# BMS_V5.net
KiCad netlist of a schematic drawn in Altium Designer
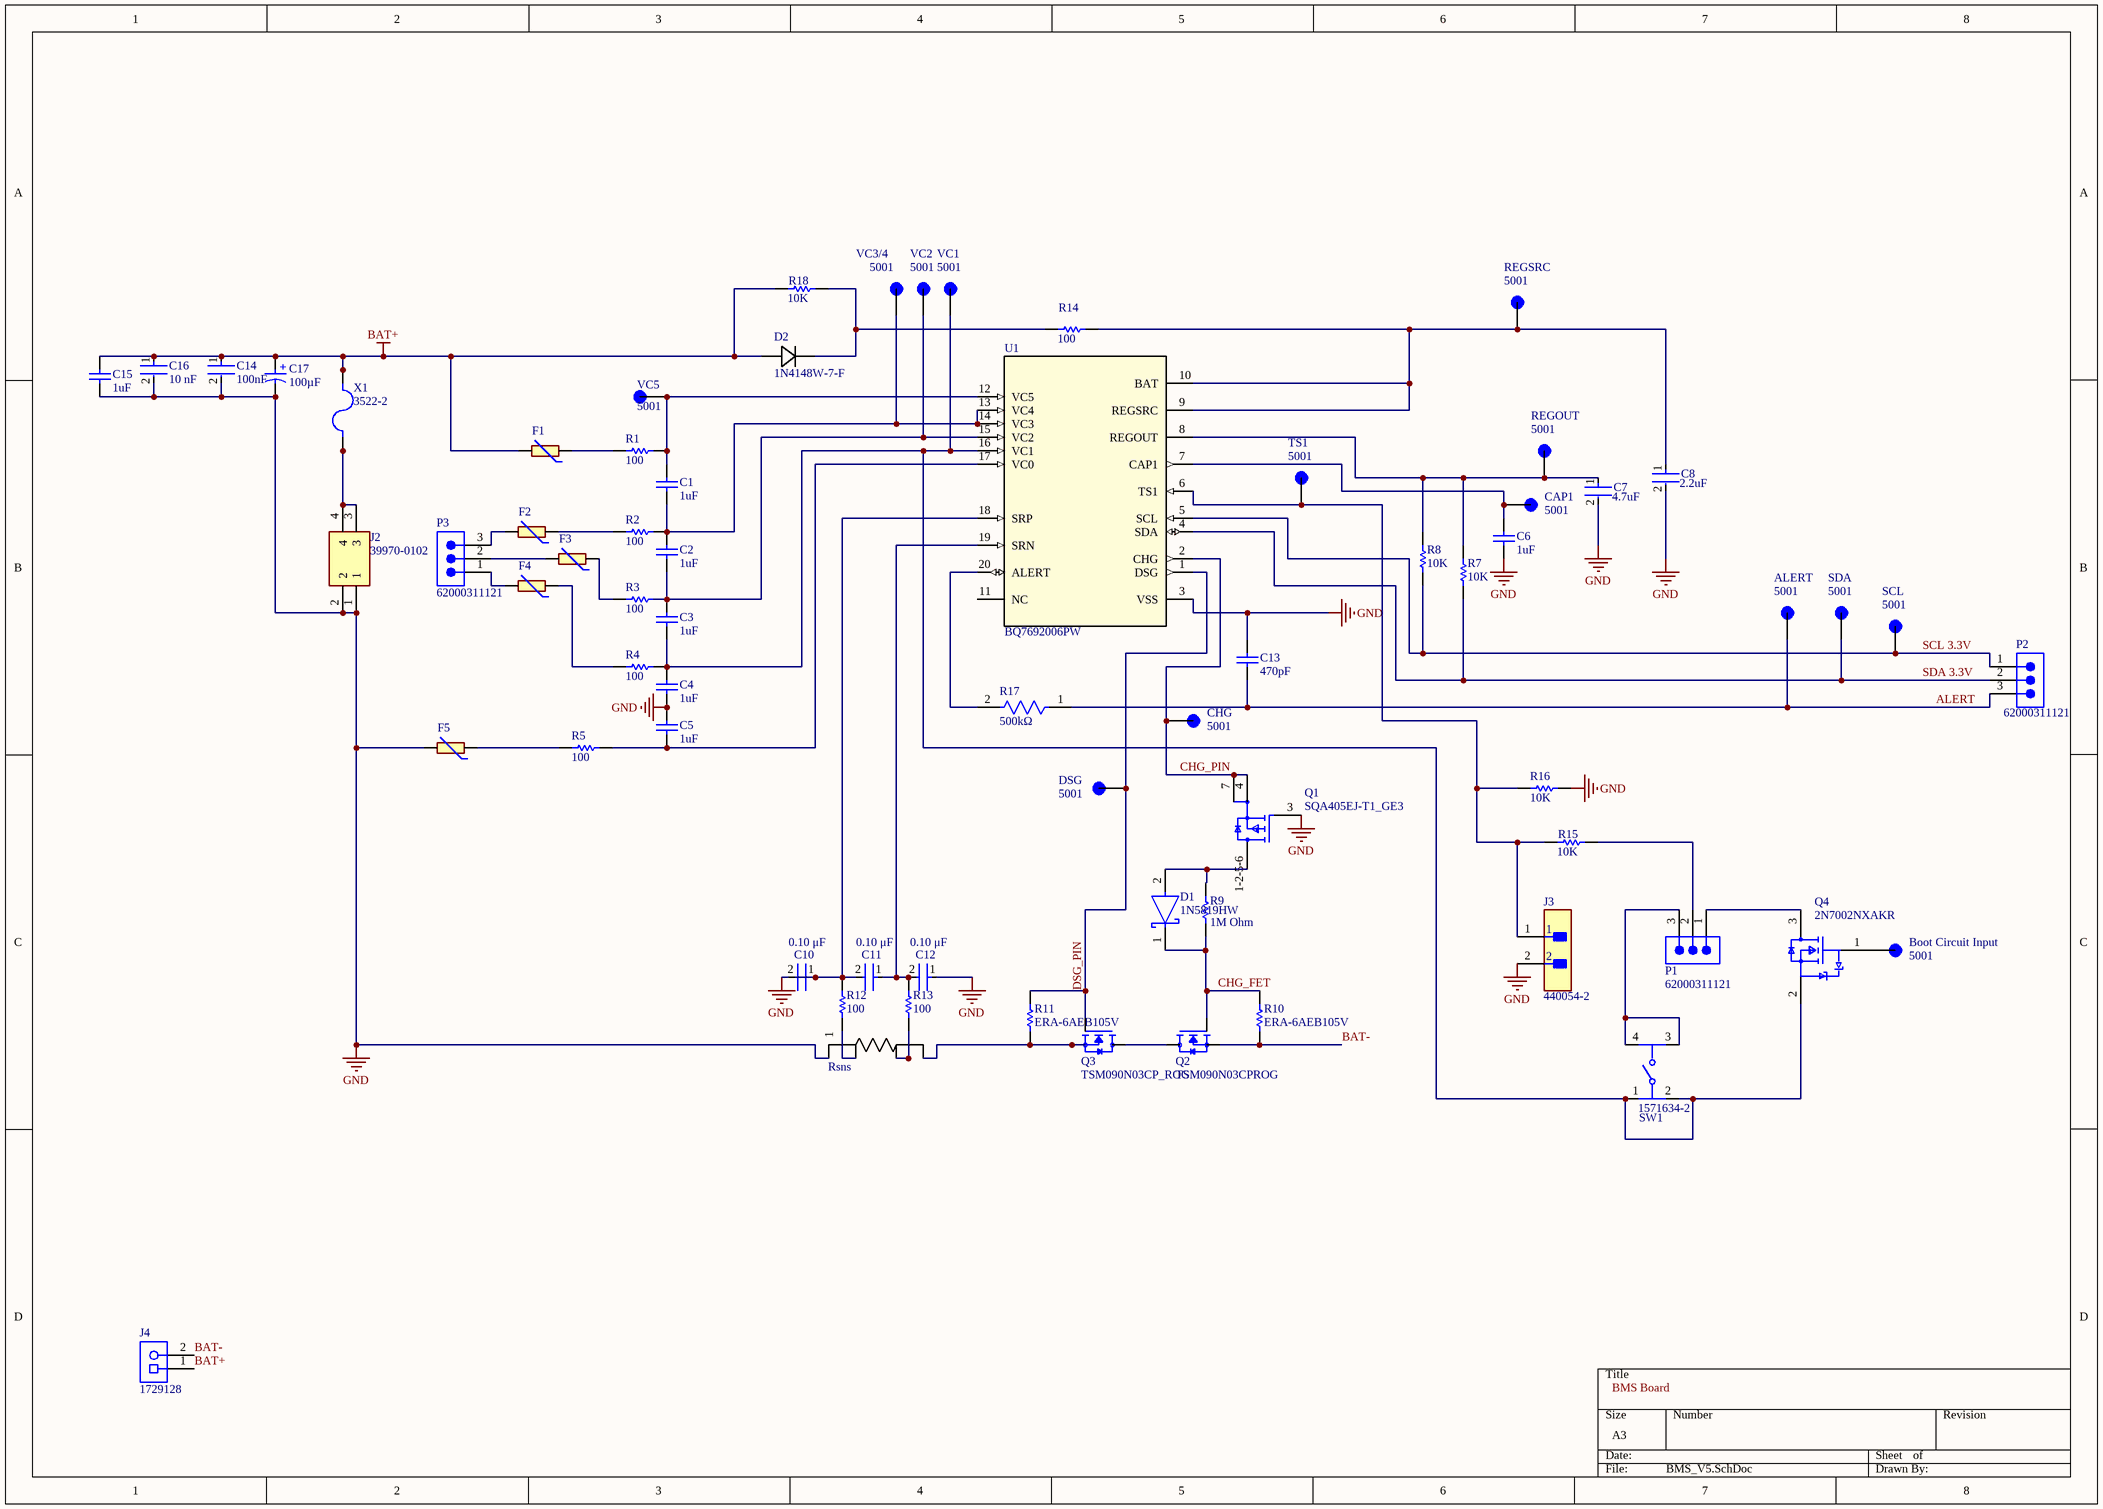
[diagram p0: BMS_V5.SchDoc]

(export (version "E")
  (design (tool "Eeschema 10.0.6"))
  (components
    (comp (ref "ALERT")
      (value "5001")
      (footprint "KEYSTONE_5001")
      (fields (field (name "MF") "Keystone Electronics"))
      (libsource (lib "5001") (part "5001"))
    )
    (comp (ref "Boot Circuit Input")
      (value "5001")
      (footprint "KEYSTONE_5001")
      (fields (field (name "MF") "Keystone Electronics"))
      (libsource (lib "5001") (part "5001"))
    )
    (comp (ref "C1")
      (value "1uF")
      (footprint "CAPC2013X140X50LL20T25")
      (fields (field (name "PART NUMBER") "C0805C105K3RACTU") (field (name "MANUFACTURER") "Kemet"))
      (libsource (lib "Altium Content Vault") (part "CAP"))
    )
    (comp (ref "C2")
      (value "1uF")
      (footprint "CAPC2013X140X50LL20T25")
      (fields (field (name "PART NUMBER") "C0805C105K3RACTU") (field (name "MANUFACTURER") "Kemet"))
      (libsource (lib "Altium Content Vault") (part "CAP"))
    )
    (comp (ref "C3")
      (value "1uF")
      (footprint "CAPC2013X140X50LL20T25")
      (fields (field (name "PART NUMBER") "C0805C105K3RACTU") (field (name "MANUFACTURER") "Kemet"))
      (libsource (lib "Altium Content Vault") (part "CAP"))
    )
    (comp (ref "C4")
      (value "1uF")
      (footprint "CAPC2013X140X50LL20T25")
      (fields (field (name "PART NUMBER") "C0805C105K3RACTU") (field (name "MANUFACTURER") "Kemet"))
      (libsource (lib "Altium Content Vault") (part "CAP"))
    )
    (comp (ref "C5")
      (value "1uF")
      (footprint "CAPC2013X140X50LL20T25")
      (fields (field (name "PART NUMBER") "C0805C105K3RACTU") (field (name "MANUFACTURER") "Kemet"))
      (libsource (lib "Altium Content Vault") (part "CAP"))
    )
    (comp (ref "C6")
      (value "1uF")
      (footprint "CAPC2013X140X50LL20T25")
      (fields (field (name "PART NUMBER") "C0805C105K3RACTU") (field (name "MANUFACTURER") "Kemet"))
      (libsource (lib "Altium Content Vault") (part "CAP"))
    )
    (comp (ref "C7")
      (value "GRM21BR61H475KE51L")
      (footprint "FP-GRM21B-0_15-IPC_B")
      (description "Chip Multilayer Ceramic Capacitors for General Purpose, 0805, 4.7uF, X5R, 15%, 10%, 50V")
      (fields (field (name "CAPACITANCE") "4.7uF") (field (name "TOLERANCE") "10%"))
      (libsource (lib "Altium Content Vault") (part "b4654b650e69147ec39a6b967a45e02"))
    )
    (comp (ref "C8")
      (value "TMK316B7225KLHT")
      (footprint "FP-1206-L_3_2_0_15-W_1_6-IPC_C")
      (description "None")
      (fields (field (name "CAPACITANCE") "2.2uF") (field (name "TOLERANCE") "10%"))
      (libsource (lib "Altium Content Vault") (part "02cd4be3c70576c341d710602a673aa"))
    )
    (comp (ref "C10")
      (value "C1206C104M4JACAUTO")
      (footprint "FP-C1206C-EB-MFG")
      (description "C1206 0.10 μF U2J 20.00% 16 V")
      (fields
        (field (name "MANUFACTURER") "KEMET")
        (field (name "TOLERANCE") "0.2")
        (field (name "CAPACITANCE") "0.10 μF")
      )
      (libsource (lib "Altium Content Vault") (part "b4654b650e69147ec39a6b967a45e02"))
    )
    (comp (ref "C11")
      (value "C1206C104M4JACAUTO")
      (footprint "FP-C1206C-EB-MFG")
      (description "C1206 0.10 μF U2J 20.00% 16 V")
      (fields
        (field (name "MANUFACTURER") "KEMET")
        (field (name "TOLERANCE") "0.2")
        (field (name "CAPACITANCE") "0.10 μF")
      )
      (libsource (lib "Altium Content Vault") (part "b4654b650e69147ec39a6b967a45e02"))
    )
    (comp (ref "C12")
      (value "C1206C104M4JACAUTO")
      (footprint "FP-C1206C-EB-MFG")
      (description "C1206 0.10 μF U2J 20.00% 16 V")
      (fields
        (field (name "MANUFACTURER") "KEMET")
        (field (name "TOLERANCE") "0.2")
        (field (name "CAPACITANCE") "0.10 μF")
      )
      (libsource (lib "Altium Content Vault") (part "b4654b650e69147ec39a6b967a45e02"))
    )
    (comp (ref "C13")
      (value "470pF")
      (footprint "CAPC2013X145X48NL20T23")
      (fields (field (name "MANUFACTURER") "Vitramon") (field (name "PART NUMBER") "VJ0805Y471KXAAC"))
      (libsource (lib "Altium Content Vault") (part "CAP"))
    )
    (comp (ref "C14")
      (value "12061C104KAZ2A")
      (footprint "FP-1206-L_3_2_0_2-W_1_6_0-MFG")
      (description "General Purpose Ceramic Capacitor, 1206, 100nF, 10%, X7R, 15%, 100V")
      (fields (field (name "TOLERANCE") "10%") (field (name "CAPACITANCE") "100nF"))
      (libsource (lib "Altium Content Vault") (part "b4654b650e69147ec39a6b967a45e02"))
    )
    (comp (ref "C15")
      (value "1uF")
      (footprint "CAPC2013X140X50LL20T25")
      (fields (field (name "PART NUMBER") "C0805C105K3RACTU") (field (name "MANUFACTURER") "Kemet"))
      (libsource (lib "Altium Content Vault") (part "CAP"))
    )
    (comp (ref "C16")
      (value "10 nF")
      (footprint "FP-CC0603-DA-MFG")
      (description "CAP CER 10000PF 50V X7R 0603")
      (fields (field (name "TOLERANCE") "0.1") (field (name "MANUFACTURER PART NUMBER") "CC0603KRX7R9BB103"))
      (libsource (lib "Altium Content Vault") (part "11868f565c42a9108669ba33697ecf6"))
    )
    (comp (ref "C17")
      (value "865080545012")
      (footprint "WCAP-ASLI_D6.3H7.7")
      (description "865080545012 Cap Aluminum Lytic 100uF 35V 20% (6.3 X 7.7mm) SMD 300mA 2000h 105C T/R")
      (fields (field (name "CAPACITANCE") "100µF") (field (name "TOLERANCE") "20%"))
      (libsource (lib "Altium Content Vault") (part "Capacitor_Polarized"))
    )
    (comp (ref "CAP1")
      (value "5001")
      (footprint "KEYSTONE_5001")
      (fields (field (name "MF") "Keystone Electronics"))
      (libsource (lib "5001") (part "5001"))
    )
    (comp (ref "CHG")
      (value "5001")
      (footprint "KEYSTONE_5001")
      (fields (field (name "MF") "Keystone Electronics"))
      (libsource (lib "5001") (part "5001"))
    )
    (comp (ref "D1")
      (value "1N5819HW")
      (footprint "FP-SOD123-IPC_A")
      (description "DIODE SCHOTTKY 40V 1A SOD123")
      (libsource (lib "Altium Content Vault") (part "1d6ec82d83fb6aee721767c19dac4b9"))
    )
    (comp (ref "D2")
      (value "1N4148W-7-F")
      (footprint "SOD123_DIO")
      (description "DIODE; SWT; SMT (SOD-123); PIV=100V; IF=0.3A; -65 DEGC TO +150 DEGC")
      (fields (field (name "COPYRIGHT") "Copyright (C) 2025 Ultra Librarian. All rights reserved."))
      (libsource (lib "1N4148W-7-F") (part "1N4148W-7-F"))
    )
    (comp (ref "DSG")
      (value "5001")
      (footprint "KEYSTONE_5001")
      (fields (field (name "MF") "Keystone Electronics"))
      (libsource (lib "5001") (part "5001"))
    )
    (comp (ref "F1")
      (value "0ZCJ0005FF2E")
      (footprint "FUSC3216X85N")
      (fields (field (name "MF") "{'manufacturer': u'Bel Fuse Inc.'}"))
      (libsource (lib "0ZCJ0005FF2E") (part "0ZCJ0005FF2E"))
    )
    (comp (ref "F2")
      (value "0ZCJ0005FF2E")
      (footprint "FUSC3216X85N")
      (fields (field (name "MF") "{'manufacturer': u'Bel Fuse Inc.'}"))
      (libsource (lib "0ZCJ0005FF2E") (part "0ZCJ0005FF2E"))
    )
    (comp (ref "F3")
      (value "0ZCJ0005FF2E")
      (footprint "FUSC3216X85N")
      (fields (field (name "MF") "{'manufacturer': u'Bel Fuse Inc.'}"))
      (libsource (lib "0ZCJ0005FF2E") (part "0ZCJ0005FF2E"))
    )
    (comp (ref "F4")
      (value "0ZCJ0005FF2E")
      (footprint "FUSC3216X85N")
      (fields (field (name "MF") "{'manufacturer': u'Bel Fuse Inc.'}"))
      (libsource (lib "0ZCJ0005FF2E") (part "0ZCJ0005FF2E"))
    )
    (comp (ref "F5")
      (value "0ZCJ0005FF2E")
      (footprint "FUSC3216X85N")
      (fields (field (name "MF") "{'manufacturer': u'Bel Fuse Inc.'}"))
      (libsource (lib "0ZCJ0005FF2E") (part "0ZCJ0005FF2E"))
    )
    (comp (ref "J2")
      (value "39970-0102")
      (footprint "399700102")
      (description "10.16mm Beau Eurostyle Fixed Mount PCB Terminal Block, High Power 40A,  Circuits")
      (fields (field (name "MOUSER PART NUMBER") "538-39970-0102"))
      (libsource (lib "39970-0102") (part "39970-0102"))
    )
    (comp (ref "J3")
      (value "440054-2")
      (footprint "FP-440054-2-MFG")
      (description "CONN HEADER VERT 2POS 2MM")
      (fields
        (field (name "MANUFACTURER") "TE Connectivity")
        (field (name "OCTOPART") "https://octopart.com/440054-2-te+connectivity-40237927")
      )
      (libsource (lib "Altium Content Vault") (part "3bc925449376181038e59eaffc5286c"))
    )
    (comp (ref "J4")
      (value "1729128")
      (footprint "PHOE-1729128-2_V")
      (description "PCB Terminal Block, 13.5 A, 400 V, 2-Pin THD, RoHS, Bulk")
      (fields (field (name "MANUFACTURER") "Phoenix Contact"))
      (libsource (lib "Altium Content Vault") (part "CN-2P-F-R2"))
    )
    (comp (ref "P1")
      (value "62000311121")
      (footprint "62000311121")
      (libsource (lib "Altium Content Vault") (part "Header_Male_1R_03P"))
    )
    (comp (ref "P2")
      (value "62000311121")
      (footprint "62000311121")
      (libsource (lib "Altium Content Vault") (part "Header_Male_1R_03P"))
    )
    (comp (ref "P3")
      (value "62000311121")
      (footprint "62000311121")
      (libsource (lib "Altium Content Vault") (part "Header_Male_1R_03P"))
    )
    (comp (ref "Q1")
      (value "SQA405EJ-T1_GE3")
      (footprint "FP-SQA405EJ-T1_GE3-MFG")
      (description "MOSFET P-CH 40V 10A PPAK SC70-6")
      (libsource (lib "Altium Content Vault") (part "bcafd61ea9f5eb7be29787bd7996e5d"))
    )
    (comp (ref "Q2")
      (value "TSM090N03CPROG")
      (footprint "TRANS_TSM090N03CPROG")
      (description "N-Channel 30 V 50A (Tc) 40W (Tc) Surface Mount TO-252 (DPAK)")
      (fields (field (name "MF") "Taiwan Semiconductor"))
      (libsource (lib "Dattu Hariharan") (part "TSM090N03CPROG"))
    )
    (comp (ref "Q3")
      (value "TSM090N03CP_ROG")
      (footprint "TRANS_TSM090N03CP_ROG")
      (libsource (lib "TSM090N03CP_ROG") (part "TSM090N03CP_ROG"))
    )
    (comp (ref "Q4")
      (value "2N7002NXAKR")
      (footprint "FP-SOT23-IPC_B")
      (description "2N7002NXAK/SOT23/TO-236AB")
      (libsource (lib "Altium Content Vault") (part "bf18956dcdab3ff4da62eb44f668dfe"))
    )
    (comp (ref "R1")
      (value "100")
      (footprint "RESC2013X60X30ML20T20")
      (fields (field (name "PART NUMBER") "RK73H2ATTD1000F") (field (name "MANUFACTURER") "KOA Speer"))
      (libsource (lib "Altium Content Vault") (part "RES"))
    )
    (comp (ref "R2")
      (value "100")
      (footprint "RESC2013X60X30ML20T20")
      (fields (field (name "PART NUMBER") "RK73H2ATTD1000F") (field (name "MANUFACTURER") "KOA Speer"))
      (libsource (lib "Altium Content Vault") (part "RES"))
    )
    (comp (ref "R3")
      (value "100")
      (footprint "RESC2013X60X30ML20T20")
      (fields (field (name "PART NUMBER") "RK73H2ATTD1000F") (field (name "MANUFACTURER") "KOA Speer"))
      (libsource (lib "Altium Content Vault") (part "RES"))
    )
    (comp (ref "R4")
      (value "100")
      (footprint "RESC2013X60X30ML20T20")
      (fields (field (name "PART NUMBER") "RK73H2ATTD1000F") (field (name "MANUFACTURER") "KOA Speer"))
      (libsource (lib "Altium Content Vault") (part "RES"))
    )
    (comp (ref "R5")
      (value "100")
      (footprint "RESC2013X60X30ML20T20")
      (fields (field (name "PART NUMBER") "RK73H2ATTD1000F") (field (name "MANUFACTURER") "KOA Speer"))
      (libsource (lib "Altium Content Vault") (part "RES"))
    )
    (comp (ref "R7")
      (value "10K")
      (footprint "RESC2013X60X35NL10T20")
      (description "Chip Resistor, 10 KOhm, +/- 1%, 0.125 W, -55 to 155 degC, 0805 (2012 Metric), RoHS, Tape and Reel")
      (fields (field (name "MANUFACTURER") "Yageo"))
      (libsource (lib "Altium Content Vault") (part "RES-2"))
    )
    (comp (ref "R8")
      (value "10K")
      (footprint "RESC2013X60X35NL10T20")
      (description "Chip Resistor, 10 KOhm, +/- 1%, 0.125 W, -55 to 155 degC, 0805 (2012 Metric), RoHS, Tape and Reel")
      (fields (field (name "MANUFACTURER") "Yageo"))
      (libsource (lib "Altium Content Vault") (part "RES-2"))
    )
    (comp (ref "R9")
      (value "1M Ohm")
      (footprint "RESC2013X60X40LL20T25")
      (fields (field (name "PART NUMBER") "ERA-6AEB105V") (field (name "MANUFACTURER") "Panasonic"))
      (libsource (lib "Altium Content Vault") (part "RES"))
    )
    (comp (ref "R10")
      (value "ERA-6AEB105V")
      (footprint "RESC2013X60X40LL20T25")
      (fields (field (name "MANUFACTURER") "Panasonic"))
      (libsource (lib "Altium Content Vault") (part "RES"))
    )
    (comp (ref "R11")
      (value "ERA-6AEB105V")
      (footprint "RESC2013X60X40LL20T25")
      (fields (field (name "MANUFACTURER") "Panasonic"))
      (libsource (lib "Altium Content Vault") (part "RES"))
    )
    (comp (ref "R12")
      (value "100")
      (footprint "RESC2013X50X30LL20T20")
      (fields (field (name "MANUFACTURER") "Vishay Dale") (field (name "PART NUMBER") "CRCW0805100RFKEA"))
      (libsource (lib "Altium Content Vault") (part "RES"))
    )
    (comp (ref "R13")
      (value "100")
      (footprint "RESC2013X50X30LL20T20")
      (fields (field (name "MANUFACTURER") "Vishay Dale") (field (name "PART NUMBER") "CRCW0805100RFKEA"))
      (libsource (lib "Altium Content Vault") (part "RES"))
    )
    (comp (ref "R14")
      (value "100")
      (footprint "RESC2013X60X30ML20T20")
      (fields (field (name "PART NUMBER") "RK73H2ATTD1000F") (field (name "MANUFACTURER") "KOA Speer"))
      (libsource (lib "Altium Content Vault") (part "RES"))
    )
    (comp (ref "R15")
      (value "10K")
      (footprint "RESC2013X60X35NL10T20")
      (description "Chip Resistor, 10 KOhm, +/- 1%, 0.125 W, -55 to 155 degC, 0805 (2012 Metric), RoHS, Tape and Reel")
      (fields (field (name "MANUFACTURER") "Yageo"))
      (libsource (lib "Altium Content Vault") (part "RES-2"))
    )
    (comp (ref "R16")
      (value "10K")
      (footprint "RESC2013X60X35NL10T20")
      (description "Chip Resistor, 10 KOhm, +/- 1%, 0.125 W, -55 to 155 degC, 0805 (2012 Metric), RoHS, Tape and Reel")
      (fields (field (name "MANUFACTURER") "Yageo"))
      (libsource (lib "Altium Content Vault") (part "RES-2"))
    )
    (comp (ref "R17")
      (value "~")
      (footprint "FP-CRMA1206-IPC_A")
      (description "CRMA1206AF500KFKEF Res Thick Film 1206 500K Ohm 1% 0.3W ±100ppm/C Pad SMD Automotive T/R")
      (fields (field (name "TOLERANCE") "1%") (field (name "RESISTANCE") "500kΩ"))
      (libsource (lib "Altium Content Vault") (part "1029c3af85768c4190bb7ad29bc67b5"))
    )
    (comp (ref "R18")
      (value "10K")
      (footprint "RESC2013X60X35NL10T20")
      (description "Chip Resistor, 10 KOhm, +/- 1%, 0.125 W, -55 to 155 degC, 0805 (2012 Metric), RoHS, Tape and Reel")
      (fields (field (name "MANUFACTURER") "Yageo"))
      (libsource (lib "Altium Content Vault") (part "RES-2"))
    )
    (comp (ref "REGOUT")
      (value "5001")
      (footprint "KEYSTONE_5001")
      (fields (field (name "MF") "Keystone Electronics"))
      (libsource (lib "5001") (part "5001"))
    )
    (comp (ref "REGSRC")
      (value "5001")
      (footprint "KEYSTONE_5001")
      (fields (field (name "MF") "Keystone Electronics"))
      (libsource (lib "5001") (part "5001"))
    )
    (comp (ref "Rsns")
      (value "WSL36375L000FEA")
      (footprint "WSL3637_VIS")
      (description "WSL-3637 .005 1% EA e3")
      (fields (field (name "COPYRIGHT") "Copyright (C) 2025 Ultra Librarian. All rights reserved."))
      (libsource (lib "Altium Learning") (part "WSL36375L000FEA"))
    )
    (comp (ref "SCL")
      (value "5001")
      (footprint "KEYSTONE_5001")
      (fields (field (name "MF") "Keystone Electronics"))
      (libsource (lib "5001") (part "5001"))
    )
    (comp (ref "SDA")
      (value "5001")
      (footprint "KEYSTONE_5001")
      (fields (field (name "MF") "Keystone Electronics"))
      (libsource (lib "5001") (part "5001"))
    )
    (comp (ref "SW1")
      (value "1571634-2")
      (footprint "FP-1571634-2-MFG")
      (description "SWITCH TACTILE SPST-NO 0.05A 24V")
      (libsource (lib "Altium Content Vault") (part "512b1658425e80dc09bd29e095ee4d3"))
    )
    (comp (ref "TS1")
      (value "5001")
      (footprint "KEYSTONE_5001")
      (fields (field (name "MF") "Keystone Electronics"))
      (libsource (lib "5001") (part "5001"))
    )
    (comp (ref "U1")
      (value "BQ7692006PW")
      (footprint "PW0020A_N")
      (description "3 to 5-Series Cell Li-Ion and Li-Phosphate Battery Monitor (bq76940 Family) 20-TSSOP -40 to 85")
      (fields (field (name "COPYRIGHT") "Copyright (C) 2025 Ultra Librarian. All rights reserved."))
      (libsource (lib "BQ7692006PW") (part "BQ7692006PW"))
    )
    (comp (ref "VC1")
      (value "5001")
      (footprint "KEYSTONE_5001")
      (fields (field (name "MF") "Keystone Electronics"))
      (libsource (lib "5001") (part "5001"))
    )
    (comp (ref "VC2")
      (value "5001")
      (footprint "KEYSTONE_5001")
      (fields (field (name "MF") "Keystone Electronics"))
      (libsource (lib "5001") (part "5001"))
    )
    (comp (ref "VC3/4")
      (value "5001")
      (footprint "KEYSTONE_5001")
      (fields (field (name "MF") "Keystone Electronics"))
      (libsource (lib "5001") (part "5001"))
    )
    (comp (ref "VC5")
      (value "5001")
      (footprint "KEYSTONE_5001")
      (fields (field (name "MF") "Keystone Electronics"))
      (libsource (lib "5001") (part "5001"))
    )
    (comp (ref "X1")
      (value "3522-2")
      (footprint "FUSE_3522-2")
      (fields (field (name "MF") "{'manufacturer': u'Keystone Electronics'}"))
      (libsource (lib "3522-2") (part "3522-2"))
    )
  )
  (nets
    (net (code "2") (name "/ALERT") (class "Default")
      (node (ref "ALERT") (pin "TP") (pinfunction "TP_TP") (pintype "passive"))
      (node (ref "C13") (pin "1") (pinfunction "1_1") (pintype "passive"))
      (node (ref "P2") (pin "3") (pinfunction "3_3") (pintype "passive"))
      (node (ref "R17") (pin "1") (pinfunction "1_1") (pintype "passive"))
    )
    (net (code "3") (name "/BAT-") (class "Default")
      (node (ref "J4") (pin "2") (pinfunction "2_2") (pintype "passive"))
      (node (ref "Q2") (pin "3") (pinfunction "S_3") (pintype "passive"))
      (node (ref "R10") (pin "1") (pinfunction "1_1") (pintype "passive"))
    )
    (net (code "4") (name "/CHG_FET") (class "Default")
      (node (ref "D1") (pin "1") (pinfunction "C_1") (pintype "passive"))
      (node (ref "Q2") (pin "1") (pinfunction "G_1") (pintype "passive"))
      (node (ref "R10") (pin "2") (pinfunction "2_2") (pintype "passive"))
      (node (ref "R9") (pin "1") (pinfunction "1_1") (pintype "passive"))
    )
    (net (code "5") (name "/CHG_PIN") (class "Default")
      (node (ref "CHG") (pin "TP") (pinfunction "TP_TP") (pintype "passive"))
      (node (ref "Q1") (pin "4") (pinfunction "S_4") (pintype "passive"))
      (node (ref "Q1") (pin "7") (pinfunction "S_7") (pintype "passive"))
      (node (ref "U1") (pin "2") (pinfunction "CHG_2") (pintype "output"))
    )
    (net (code "6") (name "/DSG_PIN") (class "Default")
      (node (ref "DSG") (pin "TP") (pinfunction "TP_TP") (pintype "passive"))
      (node (ref "Q3") (pin "1") (pinfunction "G_1") (pintype "passive"))
      (node (ref "R11") (pin "2") (pinfunction "2_2") (pintype "passive"))
      (node (ref "U1") (pin "1") (pinfunction "DSG_1") (pintype "output"))
    )
    (net (code "7") (name "/SCL 3.3V") (class "Default")
      (node (ref "P2") (pin "1") (pinfunction "1_1") (pintype "passive"))
      (node (ref "R8") (pin "1") (pinfunction "1_1") (pintype "passive"))
      (node (ref "SCL") (pin "TP") (pinfunction "TP_TP") (pintype "passive"))
      (node (ref "U1") (pin "5") (pinfunction "SCL_5") (pintype "input"))
    )
    (net (code "8") (name "/SDA 3.3V") (class "Default")
      (node (ref "P2") (pin "2") (pinfunction "2_2") (pintype "passive"))
      (node (ref "R7") (pin "1") (pinfunction "1_1") (pintype "passive"))
      (node (ref "SDA") (pin "TP") (pinfunction "TP_TP") (pintype "passive"))
      (node (ref "U1") (pin "4") (pinfunction "SDA_4") (pintype "bidirectional"))
    )
    (net (code "9") (name "BAT+") (class "Default")
      (node (ref "C14") (pin "1") (pinfunction "1_1") (pintype "passive"))
      (node (ref "C15") (pin "2") (pinfunction "2_2") (pintype "passive"))
      (node (ref "C16") (pin "1") (pinfunction "1_1") (pintype "passive"))
      (node (ref "C17") (pin "1") (pinfunction "P_1") (pintype "passive"))
      (node (ref "D2") (pin "2") (pinfunction "2_2") (pintype "passive"))
      (node (ref "F1") (pin "2") (pinfunction "2_2") (pintype "passive"))
      (node (ref "J4") (pin "1") (pinfunction "1_1") (pintype "passive"))
      (node (ref "R18") (pin "1") (pinfunction "1_1") (pintype "passive"))
      (node (ref "X1") (pin "2A") (pinfunction "2_2A") (pintype "passive"))
      (node (ref "X1") (pin "2B") (pinfunction "2_2B") (pintype "passive"))
    )
    (net (code "10") (name "GND") (class "Default")
      (node (ref "C10") (pin "2") (pinfunction "2_2") (pintype "passive"))
      (node (ref "C12") (pin "1") (pinfunction "1_1") (pintype "passive"))
      (node (ref "C13") (pin "2") (pinfunction "2_2") (pintype "passive"))
      (node (ref "C14") (pin "2") (pinfunction "2_2") (pintype "passive"))
      (node (ref "C15") (pin "1") (pinfunction "1_1") (pintype "passive"))
      (node (ref "C16") (pin "2") (pinfunction "2_2") (pintype "passive"))
      (node (ref "C17") (pin "2") (pinfunction "N_2") (pintype "passive"))
      (node (ref "C4") (pin "1") (pinfunction "1_1") (pintype "passive"))
      (node (ref "C5") (pin "2") (pinfunction "2_2") (pintype "passive"))
      (node (ref "C6") (pin "1") (pinfunction "1_1") (pintype "passive"))
      (node (ref "C7") (pin "2") (pinfunction "2_2") (pintype "passive"))
      (node (ref "C8") (pin "2") (pinfunction "2_2") (pintype "passive"))
      (node (ref "F5") (pin "2") (pinfunction "2_2") (pintype "passive"))
      (node (ref "J2") (pin "1") (pinfunction "1_1") (pintype "passive"))
      (node (ref "J2") (pin "2") (pinfunction "2_2") (pintype "passive"))
      (node (ref "J3") (pin "2") (pinfunction "2_2") (pintype "passive"))
      (node (ref "Q1") (pin "3") (pinfunction "G_3") (pintype "passive"))
      (node (ref "R16") (pin "2") (pinfunction "2_2") (pintype "passive"))
      (node (ref "Rsns") (pin "1") (pinfunction "1_1") (pintype "passive"))
      (node (ref "U1") (pin "3") (pinfunction "VSS_3") (pintype "power_in"))
    )
    (net (code "11") (name "Net-(D1-A)") (class "Default")
      (node (ref "D1") (pin "2") (pinfunction "A_2") (pintype "passive"))
      (node (ref "Q1") (pin "1-2-5-6") (pinfunction "D_1-2-5-6") (pintype "passive"))
      (node (ref "R9") (pin "2") (pinfunction "2_2") (pintype "passive"))
    )
    (net (code "12") (name "Net-(D2-Pad1)") (class "Default")
      (node (ref "D2") (pin "1") (pinfunction "1_1") (pintype "passive"))
      (node (ref "R14") (pin "2") (pinfunction "2_2") (pintype "passive"))
      (node (ref "R18") (pin "2") (pinfunction "2_2") (pintype "passive"))
    )
    (net (code "13") (name "Net-(F1-Pad1)") (class "Default")
      (node (ref "F1") (pin "1") (pinfunction "1_1") (pintype "passive"))
      (node (ref "R1") (pin "1") (pinfunction "1_1") (pintype "passive"))
    )
    (net (code "14") (name "Net-(F2-Pad1)") (class "Default")
      (node (ref "F2") (pin "1") (pinfunction "1_1") (pintype "passive"))
      (node (ref "R2") (pin "1") (pinfunction "1_1") (pintype "passive"))
    )
    (net (code "15") (name "Net-(F2-Pad2)") (class "Default")
      (node (ref "F2") (pin "2") (pinfunction "2_2") (pintype "passive"))
      (node (ref "P3") (pin "3") (pinfunction "3_3") (pintype "passive"))
    )
    (net (code "16") (name "Net-(F3-Pad1)") (class "Default")
      (node (ref "F3") (pin "1") (pinfunction "1_1") (pintype "passive"))
      (node (ref "R3") (pin "1") (pinfunction "1_1") (pintype "passive"))
    )
    (net (code "17") (name "Net-(F3-Pad2)") (class "Default")
      (node (ref "F3") (pin "2") (pinfunction "2_2") (pintype "passive"))
      (node (ref "P3") (pin "2") (pinfunction "2_2") (pintype "passive"))
    )
    (net (code "18") (name "Net-(F4-Pad1)") (class "Default")
      (node (ref "F4") (pin "1") (pinfunction "1_1") (pintype "passive"))
      (node (ref "R4") (pin "1") (pinfunction "1_1") (pintype "passive"))
    )
    (net (code "19") (name "Net-(F4-Pad2)") (class "Default")
      (node (ref "F4") (pin "2") (pinfunction "2_2") (pintype "passive"))
      (node (ref "P3") (pin "1") (pinfunction "1_1") (pintype "passive"))
    )
    (net (code "20") (name "Net-(F5-Pad1)") (class "Default")
      (node (ref "F5") (pin "1") (pinfunction "1_1") (pintype "passive"))
      (node (ref "R5") (pin "1") (pinfunction "1_1") (pintype "passive"))
    )
    (net (code "21") (name "Net-(J2-Pad3)") (class "Default")
      (node (ref "J2") (pin "3") (pinfunction "3_3") (pintype "passive"))
      (node (ref "J2") (pin "4") (pinfunction "4_4") (pintype "passive"))
      (node (ref "X1") (pin "1A") (pinfunction "1_1A") (pintype "passive"))
      (node (ref "X1") (pin "1B") (pinfunction "1_1B") (pintype "passive"))
    )
    (net (code "22") (name "Net-(P1-Pad2)") (class "Default")
      (node (ref "P1") (pin "2") (pinfunction "2_2") (pintype "passive"))
      (node (ref "R15") (pin "2") (pinfunction "2_2") (pintype "passive"))
    )
    (net (code "23") (name "Net-(P1-Pad3)") (class "Default")
      (node (ref "P1") (pin "3") (pinfunction "3_3") (pintype "passive"))
      (node (ref "SW1") (pin "3") (pinfunction "3_3") (pintype "passive"))
      (node (ref "SW1") (pin "4") (pinfunction "4_4") (pintype "passive"))
    )
    (net (code "24") (name "Net-(Q2-D)") (class "Default")
      (node (ref "Q2") (pin "2") (pinfunction "D_2") (pintype "passive"))
      (node (ref "Q3") (pin "2") (pinfunction "D_2") (pintype "passive"))
    )
    (net (code "25") (name "Net-(Q3-S)") (class "Default")
      (node (ref "Q3") (pin "3") (pinfunction "S_3") (pintype "passive"))
      (node (ref "R11") (pin "1") (pinfunction "1_1") (pintype "passive"))
      (node (ref "Rsns") (pin "4") (pinfunction "4_4") (pintype "passive"))
    )
    (net (code "26") (name "Net-(Q4-D)") (class "Default")
      (node (ref "P1") (pin "1") (pinfunction "1_1") (pintype "passive"))
      (node (ref "Q4") (pin "3") (pinfunction "D_3") (pintype "passive"))
    )
    (net (code "27") (name "Net-(Q4-G)") (class "Default")
      (node (ref "Boot Circuit Input") (pin "TP") (pinfunction "TP_TP") (pintype "passive"))
      (node (ref "Q4") (pin "1") (pinfunction "G_1") (pintype "passive"))
    )
    (net (code "28") (name "Net-(Q4-S)") (class "Default")
      (node (ref "C3") (pin "1") (pinfunction "1_1") (pintype "passive"))
      (node (ref "C4") (pin "2") (pinfunction "2_2") (pintype "passive"))
      (node (ref "Q4") (pin "2") (pinfunction "S_2") (pintype "passive"))
      (node (ref "R4") (pin "2") (pinfunction "2_2") (pintype "passive"))
      (node (ref "SW1") (pin "1") (pinfunction "1_1") (pintype "passive"))
      (node (ref "SW1") (pin "2") (pinfunction "2_2") (pintype "passive"))
      (node (ref "U1") (pin "16") (pinfunction "VC1_16") (pintype "input"))
      (node (ref "VC1") (pin "TP") (pinfunction "TP_TP") (pintype "passive"))
    )
    (net (code "29") (name "Net-(R12-Pad1)") (class "Default")
      (node (ref "R12") (pin "1") (pinfunction "1_1") (pintype "passive"))
      (node (ref "Rsns") (pin "2") (pinfunction "2_2") (pintype "passive"))
    )
    (net (code "30") (name "Net-(R13-Pad1)") (class "Default")
      (node (ref "R13") (pin "1") (pinfunction "1_1") (pintype "passive"))
      (node (ref "Rsns") (pin "3") (pinfunction "3_3") (pintype "passive"))
    )
    (net (code "31") (name "Net-(U1-ALERT)") (class "Default")
      (node (ref "R17") (pin "2") (pinfunction "2_2") (pintype "passive"))
      (node (ref "U1") (pin "20") (pinfunction "ALERT_20") (pintype "bidirectional"))
    )
    (net (code "32") (name "Net-(U1-BAT)") (class "Default")
      (node (ref "C8") (pin "1") (pinfunction "1_1") (pintype "passive"))
      (node (ref "R14") (pin "1") (pinfunction "1_1") (pintype "passive"))
      (node (ref "REGSRC") (pin "TP") (pinfunction "TP_TP") (pintype "passive"))
      (node (ref "U1") (pin "10") (pinfunction "BAT_10") (pintype "power_in"))
      (node (ref "U1") (pin "9") (pinfunction "REGSRC_9") (pintype "power_in"))
    )
    (net (code "33") (name "Net-(U1-CAP1)") (class "Default")
      (node (ref "C6") (pin "2") (pinfunction "2_2") (pintype "passive"))
      (node (ref "CAP1") (pin "TP") (pinfunction "TP_TP") (pintype "passive"))
      (node (ref "U1") (pin "7") (pinfunction "CAP1_7") (pintype "output"))
    )
    (net (code "34") (name "Net-(U1-REGOUT)") (class "Default")
      (node (ref "C7") (pin "1") (pinfunction "1_1") (pintype "passive"))
      (node (ref "R7") (pin "2") (pinfunction "2_2") (pintype "passive"))
      (node (ref "R8") (pin "2") (pinfunction "2_2") (pintype "passive"))
      (node (ref "REGOUT") (pin "TP") (pinfunction "TP_TP") (pintype "passive"))
      (node (ref "U1") (pin "8") (pinfunction "REGOUT_8") (pintype "power_in"))
    )
    (net (code "35") (name "Net-(U1-SRN)") (class "Default")
      (node (ref "C11") (pin "1") (pinfunction "1_1") (pintype "passive"))
      (node (ref "C12") (pin "2") (pinfunction "2_2") (pintype "passive"))
      (node (ref "R13") (pin "2") (pinfunction "2_2") (pintype "passive"))
      (node (ref "U1") (pin "19") (pinfunction "SRN_19") (pintype "input"))
    )
    (net (code "36") (name "Net-(U1-SRP)") (class "Default")
      (node (ref "C10") (pin "1") (pinfunction "1_1") (pintype "passive"))
      (node (ref "C11") (pin "2") (pinfunction "2_2") (pintype "passive"))
      (node (ref "R12") (pin "2") (pinfunction "2_2") (pintype "passive"))
      (node (ref "U1") (pin "18") (pinfunction "SRP_18") (pintype "input"))
    )
    (net (code "37") (name "Net-(U1-TS1)") (class "Default")
      (node (ref "J3") (pin "1") (pinfunction "1_1") (pintype "passive"))
      (node (ref "R15") (pin "1") (pinfunction "1_1") (pintype "passive"))
      (node (ref "R16") (pin "1") (pinfunction "1_1") (pintype "passive"))
      (node (ref "TS1") (pin "TP") (pinfunction "TP_TP") (pintype "passive"))
      (node (ref "U1") (pin "6") (pinfunction "TS1_6") (pintype "input"))
    )
    (net (code "38") (name "Net-(U1-VC0)") (class "Default")
      (node (ref "C5") (pin "1") (pinfunction "1_1") (pintype "passive"))
      (node (ref "R5") (pin "2") (pinfunction "2_2") (pintype "passive"))
      (node (ref "U1") (pin "17") (pinfunction "VC0_17") (pintype "input"))
    )
    (net (code "39") (name "Net-(U1-VC2)") (class "Default")
      (node (ref "C2") (pin "1") (pinfunction "1_1") (pintype "passive"))
      (node (ref "C3") (pin "2") (pinfunction "2_2") (pintype "passive"))
      (node (ref "R3") (pin "2") (pinfunction "2_2") (pintype "passive"))
      (node (ref "U1") (pin "15") (pinfunction "VC2_15") (pintype "input"))
      (node (ref "VC2") (pin "TP") (pinfunction "TP_TP") (pintype "passive"))
    )
    (net (code "40") (name "Net-(U1-VC3)") (class "Default")
      (node (ref "C1") (pin "1") (pinfunction "1_1") (pintype "passive"))
      (node (ref "C2") (pin "2") (pinfunction "2_2") (pintype "passive"))
      (node (ref "R2") (pin "2") (pinfunction "2_2") (pintype "passive"))
      (node (ref "U1") (pin "13") (pinfunction "VC4_13") (pintype "input"))
      (node (ref "U1") (pin "14") (pinfunction "VC3_14") (pintype "input"))
      (node (ref "VC3/4") (pin "TP") (pinfunction "TP_TP") (pintype "passive"))
    )
    (net (code "41") (name "Net-(U1-VC5)") (class "Default")
      (node (ref "C1") (pin "2") (pinfunction "2_2") (pintype "passive"))
      (node (ref "R1") (pin "2") (pinfunction "2_2") (pintype "passive"))
      (node (ref "U1") (pin "12") (pinfunction "VC5_12") (pintype "input"))
      (node (ref "VC5") (pin "TP") (pinfunction "TP_TP") (pintype "passive"))
    )
    (net (code "42") (name "unconnected-(U1-NC-Pad11)") (class "Default")
      (node (ref "U1") (pin "11") (pinfunction "NC_11") (pintype "passive"))
    )
  )
)
